# Signal_and_supply.net
KiCad netlist of a schematic drawn in Altium Designer
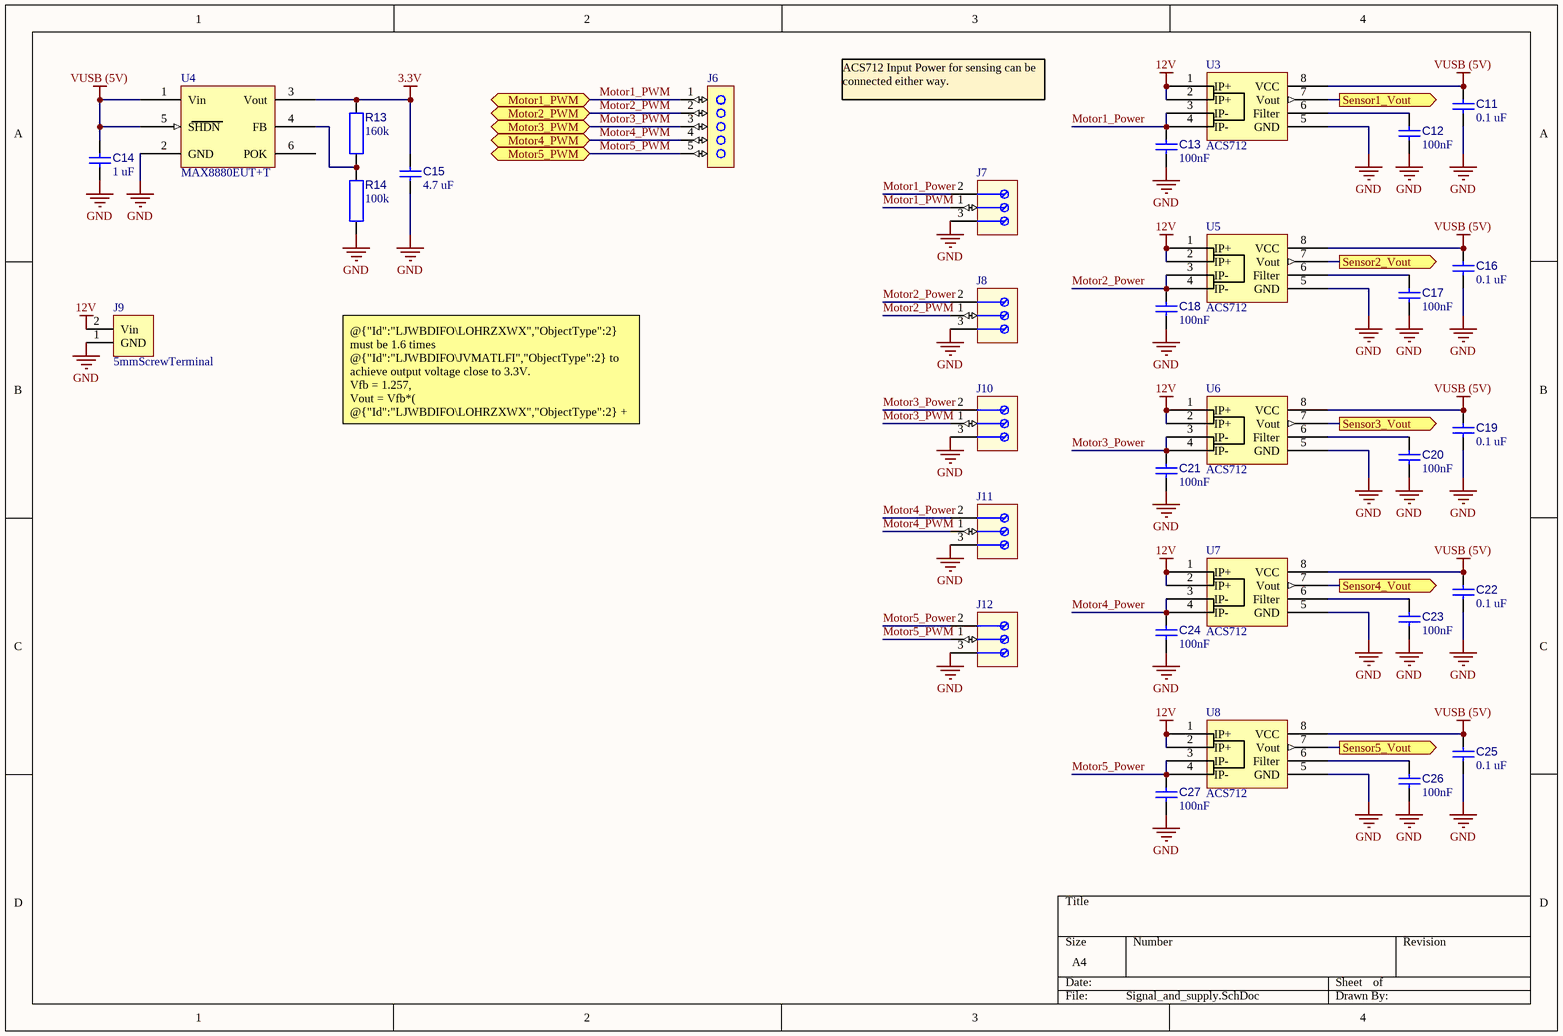
[diagram p0: Signal_and_supply.SchDoc]

(export (version "E")
  (design (tool "Eeschema 10.0.6"))
  (components
    (comp (ref "C11")
      (value "Capacitor 0603 generic")
      (footprint "CAPC1608X08N")
      (description "Generic 0603 capacitor. No set voltage/capacitance rating.")
      (fields (field (name "CAPACITANCE") "0.1 uF"))
      (libsource (lib "Martin Kaur") (part "CAP-0603"))
    )
    (comp (ref "C12")
      (value "100nF")
      (footprint "CAPC1608X90X40NL10T20")
      (description "Chip Capacitor, 100 nF, +/- 10%, 50 V, 0603 (1608 Metric)")
      (fields (field (name "TOLERANCE") "10%") (field (name "Comment") "Capacitor 100 nF +/-10% 50 V 0603"))
      (libsource (lib "Andreas Meriloo") (part "CAP-NP-2"))
    )
    (comp (ref "C13")
      (value "100nF")
      (footprint "CAPC1608X90X40NL10T20")
      (description "Chip Capacitor, 100 nF, +/- 10%, 50 V, 0603 (1608 Metric)")
      (fields (field (name "TOLERANCE") "10%") (field (name "Comment") "Capacitor 100 nF +/-10% 50 V 0603"))
      (libsource (lib "Andreas Meriloo") (part "CAP-NP-2"))
    )
    (comp (ref "C14")
      (value "Capacitor 0603 generic")
      (footprint "CAPC1608X08N")
      (description "Generic 0603 capacitor. No set voltage/capacitance rating.")
      (fields (field (name "CAPACITANCE") "1 uF"))
      (libsource (lib "Martin Kaur") (part "CAP-0603"))
    )
    (comp (ref "C15")
      (value "Capacitor 0603 generic")
      (footprint "CAPC1608X08N")
      (description "Generic 0603 capacitor. No set voltage/capacitance rating.")
      (fields (field (name "CAPACITANCE") "4.7 uF"))
      (libsource (lib "Martin Kaur") (part "CAP-0603"))
    )
    (comp (ref "C16")
      (value "Capacitor 0603 generic")
      (footprint "CAPC1608X08N")
      (description "Generic 0603 capacitor. No set voltage/capacitance rating.")
      (fields (field (name "CAPACITANCE") "0.1 uF"))
      (libsource (lib "Martin Kaur") (part "CAP-0603"))
    )
    (comp (ref "C17")
      (value "100nF")
      (footprint "CAPC1608X90X40NL10T20")
      (description "Chip Capacitor, 100 nF, +/- 10%, 50 V, 0603 (1608 Metric)")
      (fields (field (name "TOLERANCE") "10%") (field (name "Comment") "Capacitor 100 nF +/-10% 50 V 0603"))
      (libsource (lib "Andreas Meriloo") (part "CAP-NP-2"))
    )
    (comp (ref "C18")
      (value "100nF")
      (footprint "CAPC1608X90X40NL10T20")
      (description "Chip Capacitor, 100 nF, +/- 10%, 50 V, 0603 (1608 Metric)")
      (fields (field (name "TOLERANCE") "10%") (field (name "Comment") "Capacitor 100 nF +/-10% 50 V 0603"))
      (libsource (lib "Andreas Meriloo") (part "CAP-NP-2"))
    )
    (comp (ref "C19")
      (value "Capacitor 0603 generic")
      (footprint "CAPC1608X08N")
      (description "Generic 0603 capacitor. No set voltage/capacitance rating.")
      (fields (field (name "CAPACITANCE") "0.1 uF"))
      (libsource (lib "Martin Kaur") (part "CAP-0603"))
    )
    (comp (ref "C20")
      (value "100nF")
      (footprint "CAPC1608X90X40NL10T20")
      (description "Chip Capacitor, 100 nF, +/- 10%, 50 V, 0603 (1608 Metric)")
      (fields (field (name "TOLERANCE") "10%") (field (name "Comment") "Capacitor 100 nF +/-10% 50 V 0603"))
      (libsource (lib "Andreas Meriloo") (part "CAP-NP-2"))
    )
    (comp (ref "C21")
      (value "100nF")
      (footprint "CAPC1608X90X40NL10T20")
      (description "Chip Capacitor, 100 nF, +/- 10%, 50 V, 0603 (1608 Metric)")
      (fields (field (name "TOLERANCE") "10%") (field (name "Comment") "Capacitor 100 nF +/-10% 50 V 0603"))
      (libsource (lib "Andreas Meriloo") (part "CAP-NP-2"))
    )
    (comp (ref "C22")
      (value "Capacitor 0603 generic")
      (footprint "CAPC1608X08N")
      (description "Generic 0603 capacitor. No set voltage/capacitance rating.")
      (fields (field (name "CAPACITANCE") "0.1 uF"))
      (libsource (lib "Martin Kaur") (part "CAP-0603"))
    )
    (comp (ref "C23")
      (value "100nF")
      (footprint "CAPC1608X90X40NL10T20")
      (description "Chip Capacitor, 100 nF, +/- 10%, 50 V, 0603 (1608 Metric)")
      (fields (field (name "TOLERANCE") "10%") (field (name "Comment") "Capacitor 100 nF +/-10% 50 V 0603"))
      (libsource (lib "Andreas Meriloo") (part "CAP-NP-2"))
    )
    (comp (ref "C24")
      (value "100nF")
      (footprint "CAPC1608X90X40NL10T20")
      (description "Chip Capacitor, 100 nF, +/- 10%, 50 V, 0603 (1608 Metric)")
      (fields (field (name "TOLERANCE") "10%") (field (name "Comment") "Capacitor 100 nF +/-10% 50 V 0603"))
      (libsource (lib "Andreas Meriloo") (part "CAP-NP-2"))
    )
    (comp (ref "C25")
      (value "Capacitor 0603 generic")
      (footprint "CAPC1608X08N")
      (description "Generic 0603 capacitor. No set voltage/capacitance rating.")
      (fields (field (name "CAPACITANCE") "0.1 uF"))
      (libsource (lib "Martin Kaur") (part "CAP-0603"))
    )
    (comp (ref "C26")
      (value "100nF")
      (footprint "CAPC1608X90X40NL10T20")
      (description "Chip Capacitor, 100 nF, +/- 10%, 50 V, 0603 (1608 Metric)")
      (fields (field (name "TOLERANCE") "10%") (field (name "Comment") "Capacitor 100 nF +/-10% 50 V 0603"))
      (libsource (lib "Andreas Meriloo") (part "CAP-NP-2"))
    )
    (comp (ref "C27")
      (value "100nF")
      (footprint "CAPC1608X90X40NL10T20")
      (description "Chip Capacitor, 100 nF, +/- 10%, 50 V, 0603 (1608 Metric)")
      (fields (field (name "TOLERANCE") "10%") (field (name "Comment") "Capacitor 100 nF +/-10% 50 V 0603"))
      (libsource (lib "Andreas Meriloo") (part "CAP-NP-2"))
    )
    (comp (ref "J6")
      (value "Header-2.54-ZL201-05G")
      (footprint "Header-2.54-ZL201-05G-Footprint-1")
      (description "Male header, pitch 2.54 mm, 1x5 pins")
      (libsource (lib "Martin Kaur") (part "Header-2.54-ZL201-05G"))
    )
    (comp (ref "J7")
      (value "691103110003")
      (footprint "691103110003")
      (description "Barrier Strip Terminal Block")
      (libsource (lib "Martin Kaur") (part "Terminal"))
    )
    (comp (ref "J8")
      (value "691103110003")
      (footprint "691103110003")
      (description "Barrier Strip Terminal Block")
      (libsource (lib "Martin Kaur") (part "Terminal"))
    )
    (comp (ref "J9")
      (value "5mmScrewTerminal")
      (footprint "5mmScrewTerminal-Footprint-1")
      (description "16A 5 mm pitch screw terminal, 2 sockets.")
      (libsource (lib "Martin Kaur") (part "Terminal_5mm"))
    )
    (comp (ref "J10")
      (value "691103110003")
      (footprint "691103110003")
      (description "Barrier Strip Terminal Block")
      (libsource (lib "Martin Kaur") (part "Terminal"))
    )
    (comp (ref "J11")
      (value "691103110003")
      (footprint "691103110003")
      (description "Barrier Strip Terminal Block")
      (libsource (lib "Martin Kaur") (part "Terminal"))
    )
    (comp (ref "J12")
      (value "691103110003")
      (footprint "691103110003")
      (description "Barrier Strip Terminal Block")
      (libsource (lib "Martin Kaur") (part "Terminal"))
    )
    (comp (ref "R13")
      (value "Resistor 0603 generic")
      (footprint "RESC1608X04N")
      (description "Generic 0603 resistor, no fixed value.")
      (fields (field (name "RESISTANCE") "160k"))
      (libsource (lib "Martin Kaur") (part "RES0603"))
    )
    (comp (ref "R14")
      (value "Resistor 0603 generic")
      (footprint "RESC1608X04N")
      (description "Generic 0603 resistor, no fixed value.")
      (fields (field (name "RESISTANCE") "100k"))
      (libsource (lib "Martin Kaur") (part "RES0603"))
    )
    (comp (ref "U3")
      (value "ACS712")
      (footprint "SOIC127P600X175-8N")
      (description "Integrated, Hall-Effect-Based Linear Current Sensor IC")
      (libsource (lib "Martin Kaur") (part "ACS712"))
    )
    (comp (ref "U4")
      (value "MAX8880EUT+T")
      (footprint "SOT95P280X145-6N")
      (description "Ultra-Low-IQ, Low-Dropout Linear Regulator, output 1.25 - 5.5 V.")
      (libsource (lib "Martin Kaur") (part "MAX8880EUT+T"))
    )
    (comp (ref "U5")
      (value "ACS712")
      (footprint "SOIC127P600X175-8N")
      (description "Integrated, Hall-Effect-Based Linear Current Sensor IC")
      (libsource (lib "Martin Kaur") (part "ACS712"))
    )
    (comp (ref "U6")
      (value "ACS712")
      (footprint "SOIC127P600X175-8N")
      (description "Integrated, Hall-Effect-Based Linear Current Sensor IC")
      (libsource (lib "Martin Kaur") (part "ACS712"))
    )
    (comp (ref "U7")
      (value "ACS712")
      (footprint "SOIC127P600X175-8N")
      (description "Integrated, Hall-Effect-Based Linear Current Sensor IC")
      (libsource (lib "Martin Kaur") (part "ACS712"))
    )
    (comp (ref "U8")
      (value "ACS712")
      (footprint "SOIC127P600X175-8N")
      (description "Integrated, Hall-Effect-Based Linear Current Sensor IC")
      (libsource (lib "Martin Kaur") (part "ACS712"))
    )
  )
  (nets
    (net (code "1") (name "/Motor1_PWM") (class "Default")
      (node (ref "J6") (pin "1") (pinfunction "1_1") (pintype "bidirectional"))
      (node (ref "J7") (pin "1") (pinfunction "PWM_1") (pintype "bidirectional"))
    )
    (net (code "2") (name "/Motor1_Power") (class "Default")
      (node (ref "C13") (pin "2") (pinfunction "2_2") (pintype "passive"))
      (node (ref "J7") (pin "2") (pinfunction "V+_2") (pintype "power_in"))
      (node (ref "U3") (pin "3") (pinfunction "IP-_3") (pintype "power_in"))
      (node (ref "U3") (pin "4") (pinfunction "IP-_4") (pintype "power_in"))
    )
    (net (code "3") (name "/Motor2_PWM") (class "Default")
      (node (ref "J6") (pin "2") (pinfunction "2_2") (pintype "bidirectional"))
      (node (ref "J8") (pin "1") (pinfunction "PWM_1") (pintype "bidirectional"))
    )
    (net (code "4") (name "/Motor2_Power") (class "Default")
      (node (ref "C18") (pin "2") (pinfunction "2_2") (pintype "passive"))
      (node (ref "J8") (pin "2") (pinfunction "V+_2") (pintype "power_in"))
      (node (ref "U5") (pin "3") (pinfunction "IP-_3") (pintype "power_in"))
      (node (ref "U5") (pin "4") (pinfunction "IP-_4") (pintype "power_in"))
    )
    (net (code "5") (name "/Motor3_PWM") (class "Default")
      (node (ref "J10") (pin "1") (pinfunction "PWM_1") (pintype "bidirectional"))
      (node (ref "J6") (pin "3") (pinfunction "3_3") (pintype "bidirectional"))
    )
    (net (code "6") (name "/Motor3_Power") (class "Default")
      (node (ref "C21") (pin "2") (pinfunction "2_2") (pintype "passive"))
      (node (ref "J10") (pin "2") (pinfunction "V+_2") (pintype "power_in"))
      (node (ref "U6") (pin "3") (pinfunction "IP-_3") (pintype "power_in"))
      (node (ref "U6") (pin "4") (pinfunction "IP-_4") (pintype "power_in"))
    )
    (net (code "7") (name "/Motor4_PWM") (class "Default")
      (node (ref "J11") (pin "1") (pinfunction "PWM_1") (pintype "bidirectional"))
      (node (ref "J6") (pin "4") (pinfunction "4_4") (pintype "bidirectional"))
    )
    (net (code "8") (name "/Motor4_Power") (class "Default")
      (node (ref "C24") (pin "2") (pinfunction "2_2") (pintype "passive"))
      (node (ref "J11") (pin "2") (pinfunction "V+_2") (pintype "power_in"))
      (node (ref "U7") (pin "3") (pinfunction "IP-_3") (pintype "power_in"))
      (node (ref "U7") (pin "4") (pinfunction "IP-_4") (pintype "power_in"))
    )
    (net (code "9") (name "/Motor5_PWM") (class "Default")
      (node (ref "J12") (pin "1") (pinfunction "PWM_1") (pintype "bidirectional"))
      (node (ref "J6") (pin "5") (pinfunction "5_5") (pintype "bidirectional"))
    )
    (net (code "10") (name "/Motor5_Power") (class "Default")
      (node (ref "C27") (pin "2") (pinfunction "2_2") (pintype "passive"))
      (node (ref "J12") (pin "2") (pinfunction "V+_2") (pintype "power_in"))
      (node (ref "U8") (pin "3") (pinfunction "IP-_3") (pintype "power_in"))
      (node (ref "U8") (pin "4") (pinfunction "IP-_4") (pintype "power_in"))
    )
    (net (code "11") (name "/Sensor1_Vout") (class "Default")
      (node (ref "U3") (pin "7") (pinfunction "Vout_7") (pintype "output"))
    )
    (net (code "12") (name "/Sensor2_Vout") (class "Default")
      (node (ref "U5") (pin "7") (pinfunction "Vout_7") (pintype "output"))
    )
    (net (code "13") (name "/Sensor3_Vout") (class "Default")
      (node (ref "U6") (pin "7") (pinfunction "Vout_7") (pintype "output"))
    )
    (net (code "14") (name "/Sensor4_Vout") (class "Default")
      (node (ref "U7") (pin "7") (pinfunction "Vout_7") (pintype "output"))
    )
    (net (code "15") (name "/Sensor5_Vout") (class "Default")
      (node (ref "U8") (pin "7") (pinfunction "Vout_7") (pintype "output"))
    )
    (net (code "16") (name "3.3V") (class "Default")
      (node (ref "C15") (pin "1") (pinfunction "1_1") (pintype "passive"))
      (node (ref "R13") (pin "1") (pinfunction "1_1") (pintype "passive"))
      (node (ref "U4") (pin "3") (pinfunction "Vout_3") (pintype "power_in"))
    )
    (net (code "17") (name "12V") (class "Default")
      (node (ref "J9") (pin "2") (pinfunction "Vin_2") (pintype "power_in"))
      (node (ref "U3") (pin "1") (pinfunction "IP+_1") (pintype "power_in"))
      (node (ref "U3") (pin "2") (pinfunction "IP+_2") (pintype "power_in"))
      (node (ref "U5") (pin "1") (pinfunction "IP+_1") (pintype "power_in"))
      (node (ref "U5") (pin "2") (pinfunction "IP+_2") (pintype "power_in"))
      (node (ref "U6") (pin "1") (pinfunction "IP+_1") (pintype "power_in"))
      (node (ref "U6") (pin "2") (pinfunction "IP+_2") (pintype "power_in"))
      (node (ref "U7") (pin "1") (pinfunction "IP+_1") (pintype "power_in"))
      (node (ref "U7") (pin "2") (pinfunction "IP+_2") (pintype "power_in"))
      (node (ref "U8") (pin "1") (pinfunction "IP+_1") (pintype "power_in"))
      (node (ref "U8") (pin "2") (pinfunction "IP+_2") (pintype "power_in"))
    )
    (net (code "18") (name "GND") (class "Default")
      (node (ref "C11") (pin "2") (pinfunction "2_2") (pintype "passive"))
      (node (ref "C12") (pin "1") (pinfunction "1_1") (pintype "passive"))
      (node (ref "C13") (pin "1") (pinfunction "1_1") (pintype "passive"))
      (node (ref "C14") (pin "1") (pinfunction "1_1") (pintype "passive"))
      (node (ref "C15") (pin "2") (pinfunction "2_2") (pintype "passive"))
      (node (ref "C16") (pin "2") (pinfunction "2_2") (pintype "passive"))
      (node (ref "C17") (pin "1") (pinfunction "1_1") (pintype "passive"))
      (node (ref "C18") (pin "1") (pinfunction "1_1") (pintype "passive"))
      (node (ref "C19") (pin "2") (pinfunction "2_2") (pintype "passive"))
      (node (ref "C20") (pin "1") (pinfunction "1_1") (pintype "passive"))
      (node (ref "C21") (pin "1") (pinfunction "1_1") (pintype "passive"))
      (node (ref "C22") (pin "2") (pinfunction "2_2") (pintype "passive"))
      (node (ref "C23") (pin "1") (pinfunction "1_1") (pintype "passive"))
      (node (ref "C24") (pin "1") (pinfunction "1_1") (pintype "passive"))
      (node (ref "C25") (pin "2") (pinfunction "2_2") (pintype "passive"))
      (node (ref "C26") (pin "1") (pinfunction "1_1") (pintype "passive"))
      (node (ref "C27") (pin "1") (pinfunction "1_1") (pintype "passive"))
      (node (ref "J10") (pin "3") (pinfunction "GND_3") (pintype "power_in"))
      (node (ref "J11") (pin "3") (pinfunction "GND_3") (pintype "power_in"))
      (node (ref "J12") (pin "3") (pinfunction "GND_3") (pintype "power_in"))
      (node (ref "J7") (pin "3") (pinfunction "GND_3") (pintype "power_in"))
      (node (ref "J8") (pin "3") (pinfunction "GND_3") (pintype "power_in"))
      (node (ref "J9") (pin "1") (pinfunction "GND_1") (pintype "power_in"))
      (node (ref "R14") (pin "2") (pinfunction "2_2") (pintype "passive"))
      (node (ref "U3") (pin "5") (pinfunction "GND_5") (pintype "power_in"))
      (node (ref "U4") (pin "2") (pinfunction "GND_2") (pintype "power_in"))
      (node (ref "U5") (pin "5") (pinfunction "GND_5") (pintype "power_in"))
      (node (ref "U6") (pin "5") (pinfunction "GND_5") (pintype "power_in"))
      (node (ref "U7") (pin "5") (pinfunction "GND_5") (pintype "power_in"))
      (node (ref "U8") (pin "5") (pinfunction "GND_5") (pintype "power_in"))
    )
    (net (code "19") (name "Net-(U3-Filter)") (class "Default")
      (node (ref "C12") (pin "2") (pinfunction "2_2") (pintype "passive"))
      (node (ref "U3") (pin "6") (pinfunction "Filter_6") (pintype "passive"))
    )
    (net (code "20") (name "Net-(U4-FB)") (class "Default")
      (node (ref "R13") (pin "2") (pinfunction "2_2") (pintype "passive"))
      (node (ref "R14") (pin "1") (pinfunction "1_1") (pintype "passive"))
      (node (ref "U4") (pin "4") (pinfunction "FB_4") (pintype "passive"))
    )
    (net (code "21") (name "Net-(U5-Filter)") (class "Default")
      (node (ref "C17") (pin "2") (pinfunction "2_2") (pintype "passive"))
      (node (ref "U5") (pin "6") (pinfunction "Filter_6") (pintype "passive"))
    )
    (net (code "22") (name "Net-(U6-Filter)") (class "Default")
      (node (ref "C20") (pin "2") (pinfunction "2_2") (pintype "passive"))
      (node (ref "U6") (pin "6") (pinfunction "Filter_6") (pintype "passive"))
    )
    (net (code "23") (name "Net-(U7-Filter)") (class "Default")
      (node (ref "C23") (pin "2") (pinfunction "2_2") (pintype "passive"))
      (node (ref "U7") (pin "6") (pinfunction "Filter_6") (pintype "passive"))
    )
    (net (code "24") (name "Net-(U8-Filter)") (class "Default")
      (node (ref "C26") (pin "2") (pinfunction "2_2") (pintype "passive"))
      (node (ref "U8") (pin "6") (pinfunction "Filter_6") (pintype "passive"))
    )
    (net (code "25") (name "VUSB (5V)") (class "Default")
      (node (ref "C11") (pin "1") (pinfunction "1_1") (pintype "passive"))
      (node (ref "C14") (pin "2") (pinfunction "2_2") (pintype "passive"))
      (node (ref "C16") (pin "1") (pinfunction "1_1") (pintype "passive"))
      (node (ref "C19") (pin "1") (pinfunction "1_1") (pintype "passive"))
      (node (ref "C22") (pin "1") (pinfunction "1_1") (pintype "passive"))
      (node (ref "C25") (pin "1") (pinfunction "1_1") (pintype "passive"))
      (node (ref "U3") (pin "8") (pinfunction "VCC_8") (pintype "power_in"))
      (node (ref "U4") (pin "1") (pinfunction "Vin_1") (pintype "power_in"))
      (node (ref "U4") (pin "5") (pinfunction "SHDN_5") (pintype "input"))
      (node (ref "U5") (pin "8") (pinfunction "VCC_8") (pintype "power_in"))
      (node (ref "U6") (pin "8") (pinfunction "VCC_8") (pintype "power_in"))
      (node (ref "U7") (pin "8") (pinfunction "VCC_8") (pintype "power_in"))
      (node (ref "U8") (pin "8") (pinfunction "VCC_8") (pintype "power_in"))
    )
    (net (code "26") (name "unconnected-(U4-POK-Pad6)") (class "Default")
      (node (ref "U4") (pin "6") (pinfunction "POK_6") (pintype "open_emitter"))
    )
  )
)
